# DiffAmp.net
KiCad netlist of a schematic drawn in Altium Designer
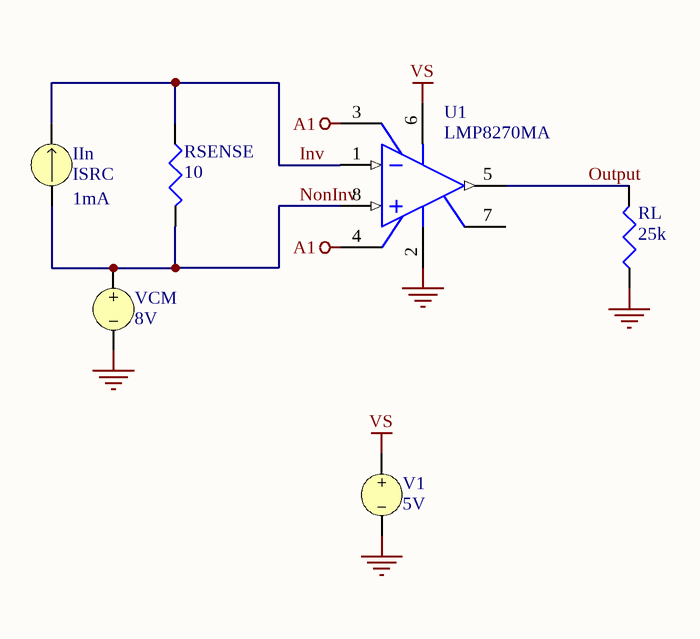
[diagram p0: DiffAmp.schdoc]

(export (version "E")
  (design (tool "Eeschema 10.0.6"))
  (components
    (comp (ref "IIn")
      (value "ISRC")
      (description "Current Source")
      (fields (field (name "AC MAGNITUDE") "1mA") (field (name "PUBLISHER") "Altium Limited"))
      (libsource (lib "Simulation Sources") (part "ISRC"))
    )
    (comp (ref "RL") (value "25k") (description "Resistor") (libsource (lib "*") (part "RES")))
    (comp (ref "RSENSE")
      (value "10")
      (description "Resistor")
      (fields (field (name "Comment") "10k"))
      (libsource (lib "") (part "RES_1"))
    )
    (comp (ref "U1")
      (value "LMP8270MA")
      (footprint "M08A_N")
      (description "High Common Mode, Gain of 20, Precision Voltage Difference Amplifier")
      (fields
        (field (name "MANUFACTURER") "National Semiconductor")
        (field (name "DIGIKEYPARTNUMBER") "LMP8270MA-ND")
        (field (name "PUBLISHER") "Altium Limited")
      )
      (libsource (lib "NSC Amplifier with SIM models") (part "LMP8270MA"))
    )
    (comp (ref "V1")
      (value "5V")
      (description "Voltage Source")
      (fields (field (name "Comment") "12V"))
      (libsource (lib "*") (part "VSRC"))
    )
    (comp (ref "VCM")
      (value "8V")
      (description "Voltage Source")
      (fields (field (name "Comment") "12V"))
      (libsource (lib "*") (part "VSRC"))
    )
  )
  (nets
    (net (code "1") (name "/Inv") (class "Default")
      (node (ref "IIn") (pin "2") (pinfunction "2_2") (pintype "passive"))
      (node (ref "RSENSE") (pin "2") (pinfunction "BOT_2") (pintype "passive"))
      (node (ref "U1") (pin "1") (pinfunction "IN-_1") (pintype "input"))
    )
    (net (code "2") (name "/NonInv") (class "Default")
      (node (ref "IIn") (pin "1") (pinfunction "1_1") (pintype "passive"))
      (node (ref "RSENSE") (pin "1") (pinfunction "TOP_1") (pintype "passive"))
      (node (ref "U1") (pin "8") (pinfunction "IN+_8") (pintype "input"))
      (node (ref "VCM") (pin "1") (pinfunction "1_1") (pintype "passive"))
    )
    (net (code "3") (name "/Output") (class "Default")
      (node (ref "RL") (pin "1") (pinfunction "TOP_1") (pintype "passive"))
      (node (ref "U1") (pin "5") (pinfunction "OUT_5") (pintype "output"))
    )
    (net (code "4") (name "A1") (class "Default")
      (node (ref "U1") (pin "3") (pinfunction "A1_3") (pintype "passive"))
      (node (ref "U1") (pin "4") (pinfunction "A2_4") (pintype "passive"))
    )
    (net (code "5") (name "GND") (class "Default")
      (node (ref "RL") (pin "2") (pinfunction "BOT_2") (pintype "passive"))
      (node (ref "U1") (pin "2") (pinfunction "GND_2") (pintype "power_in"))
      (node (ref "V1") (pin "2") (pinfunction "2_2") (pintype "passive"))
      (node (ref "VCM") (pin "2") (pinfunction "2_2") (pintype "passive"))
    )
    (net (code "6") (name "VS") (class "Default")
      (node (ref "U1") (pin "6") (pinfunction "VS_6") (pintype "power_in"))
      (node (ref "V1") (pin "1") (pinfunction "1_1") (pintype "passive"))
    )
    (net (code "7") (name "unconnected-(U1-NC-Pad7)") (class "Default")
      (node (ref "U1") (pin "7") (pinfunction "NC_7") (pintype "passive"))
    )
  )
)
